# VoltageRegulation.net
KiCad netlist of a schematic drawn in EAGLE
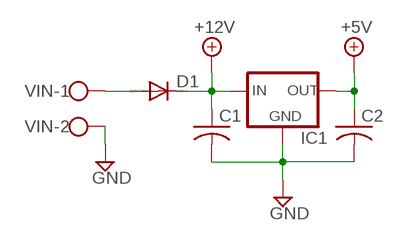
[diagram p0: schematic, sheet 1]

(export (version "E")
  (design (tool "Eeschema 10.0.6"))
  (components
    (comp (ref "C1")
      (value "C-US050-055X075")
      (footprint "eagle-import:C050-055X075")
      (libsource (lib "eagle-import") (part "C-US050-055X075"))
    )
    (comp (ref "C2")
      (value "C-US050-055X075")
      (footprint "eagle-import:C050-055X075")
      (libsource (lib "eagle-import") (part "C-US050-055X075"))
    )
    (comp (ref "D1")
      (value "DIODE-DO07")
      (footprint "eagle-import:DO07")
      (libsource (lib "eagle-import") (part "DIODE-DO07"))
    )
    (comp (ref "IC1")
      (value "78XXS")
      (footprint "eagle-import:78XXS")
      (libsource (lib "eagle-import") (part "78XXS"))
    )
    (comp (ref "VIN")
      (value "W237-102")
      (footprint "eagle-import:W237-102")
      (fields (field (name "MPN") "237-102"))
      (libsource (lib "eagle-import") (part "W237-102"))
    )
  )
  (nets
    (net (code "1") (name "+5V") (class "Default")
      (node (ref "C2") (pin "1") (pinfunction "1_1") (pintype "passive"))
      (node (ref "IC1") (pin "OUT") (pinfunction "OUT_OUT") (pintype "passive"))
    )
    (net (code "2") (name "+12V") (class "Default")
      (node (ref "C1") (pin "1") (pinfunction "1_1") (pintype "passive"))
      (node (ref "D1") (pin "C") (pinfunction "C_C") (pintype "passive"))
      (node (ref "IC1") (pin "IN") (pinfunction "IN_IN") (pintype "input"))
    )
    (net (code "3") (name "GND") (class "Default")
      (node (ref "C1") (pin "2") (pinfunction "2_2") (pintype "passive"))
      (node (ref "C2") (pin "2") (pinfunction "2_2") (pintype "passive"))
      (node (ref "IC1") (pin "GND") (pinfunction "GND_GND") (pintype "input"))
      (node (ref "VIN") (pin "2") (pinfunction "KL_2") (pintype "passive"))
    )
    (net (code "4") (name "Net-(VINA-KL)") (class "Default")
      (node (ref "D1") (pin "A") (pinfunction "A_A") (pintype "passive"))
      (node (ref "VIN") (pin "1") (pinfunction "KL_1") (pintype "passive"))
    )
  )
)
